# lm3410-sepic.net
KiCad netlist of a schematic drawn in EAGLE
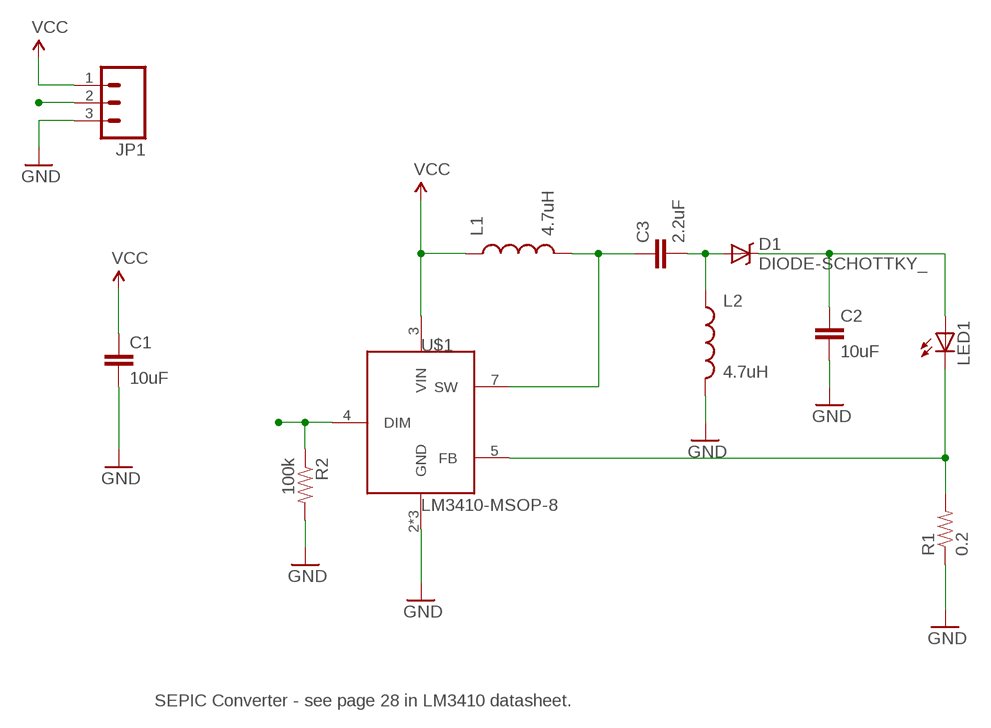
[diagram p0: schematic, sheet 1]

(export (version "E")
  (design (tool "Eeschema 10.0.6"))
  (components
    (comp (ref "C1")
      (value "10uF")
      (footprint "eagle-import:0805")
      (libsource (lib "eagle-import") (part "CAP0805"))
    )
    (comp (ref "C2")
      (value "10uF")
      (footprint "eagle-import:1206")
      (libsource (lib "eagle-import") (part "CAP1206"))
    )
    (comp (ref "C3")
      (value "2.2uF")
      (footprint "eagle-import:1206")
      (libsource (lib "eagle-import") (part "CAP1206"))
    )
    (comp (ref "D1")
      (value "DIODE-SCHOTTKY_")
      (footprint "eagle-import:SMA-DIODE")
      (libsource (lib "eagle-import") (part "DIODE-SCHOTTKY_"))
    )
    (comp (ref "JP1")
      (value "M03PTH")
      (footprint "eagle-import:1X03")
      (libsource (lib "eagle-import") (part "M03PTH"))
    )
    (comp (ref "L1")
      (value "4.7uH")
      (footprint "eagle-import:1210")
      (libsource (lib "eagle-import") (part "INDUCTOR1210"))
    )
    (comp (ref "L2")
      (value "4.7uH")
      (footprint "eagle-import:1210")
      (libsource (lib "eagle-import") (part "INDUCTOR1210"))
    )
    (comp (ref "LED1")
      (value "LED5MM")
      (footprint "eagle-import:LED5MM")
      (libsource (lib "eagle-import") (part "LED5MM"))
    )
    (comp (ref "R1")
      (value "0.2")
      (footprint "eagle-import:1206")
      (libsource (lib "eagle-import") (part "RESISTOR1206"))
    )
    (comp (ref "R2")
      (value "100k")
      (footprint "eagle-import:0805")
      (libsource (lib "eagle-import") (part "RESISTOR0805-RES"))
    )
    (comp (ref "U$1")
      (value "LM3410-MSOP-8")
      (footprint "eagle-import:MSOP-8")
      (libsource (lib "eagle-import") (part "LM3410-MSOP-8"))
    )
  )
  (nets
    (net (code "1") (name "/DIM") (class "Default")
      (node (ref "JP1") (pin "2") (pinfunction "2_2") (pintype "passive"))
      (node (ref "R2") (pin "1") (pinfunction "1_1") (pintype "passive"))
      (node (ref "U$1") (pin "4") (pinfunction "DIM_4") (pintype "bidirectional"))
    )
    (net (code "2") (name "GND") (class "Default")
      (node (ref "C1") (pin "2") (pinfunction "2_2") (pintype "passive"))
      (node (ref "C2") (pin "2") (pinfunction "2_2") (pintype "passive"))
      (node (ref "JP1") (pin "3") (pinfunction "3_3") (pintype "passive"))
      (node (ref "L2") (pin "2") (pinfunction "2_2") (pintype "passive"))
      (node (ref "R1") (pin "1") (pinfunction "1_1") (pintype "passive"))
      (node (ref "R2") (pin "2") (pinfunction "2_2") (pintype "passive"))
      (node (ref "U$1") (pin "2") (pinfunction "GND_2") (pintype "bidirectional"))
      (node (ref "U$1") (pin "6") (pinfunction "GND_6") (pintype "bidirectional"))
      (node (ref "U$1") (pin "9") (pinfunction "GND_9") (pintype "bidirectional"))
    )
    (net (code "3") (name "Net-(C2-Pad1)") (class "Default")
      (node (ref "C2") (pin "1") (pinfunction "1_1") (pintype "passive"))
      (node (ref "D1") (pin "C") (pinfunction "C_C") (pintype "passive"))
      (node (ref "LED1") (pin "A") (pinfunction "A_A") (pintype "passive"))
    )
    (net (code "4") (name "Net-(C3-Pad2)") (class "Default")
      (node (ref "C3") (pin "2") (pinfunction "2_2") (pintype "passive"))
      (node (ref "D1") (pin "A") (pinfunction "A_A") (pintype "passive"))
      (node (ref "L2") (pin "1") (pinfunction "1_1") (pintype "passive"))
    )
    (net (code "5") (name "Net-(LED1-C)") (class "Default")
      (node (ref "LED1") (pin "K") (pinfunction "C_K") (pintype "passive"))
      (node (ref "R1") (pin "2") (pinfunction "2_2") (pintype "passive"))
      (node (ref "U$1") (pin "5") (pinfunction "FB_5") (pintype "bidirectional"))
    )
    (net (code "6") (name "Net-(U$1-SW)") (class "Default")
      (node (ref "C3") (pin "1") (pinfunction "1_1") (pintype "passive"))
      (node (ref "L1") (pin "2") (pinfunction "2_2") (pintype "passive"))
      (node (ref "U$1") (pin "7") (pinfunction "SW_7") (pintype "bidirectional"))
    )
    (net (code "7") (name "VCC") (class "Default")
      (node (ref "C1") (pin "1") (pinfunction "1_1") (pintype "passive"))
      (node (ref "JP1") (pin "1") (pinfunction "1_1") (pintype "passive"))
      (node (ref "L1") (pin "1") (pinfunction "1_1") (pintype "passive"))
      (node (ref "U$1") (pin "3") (pinfunction "VIN_3") (pintype "bidirectional"))
    )
  )
)
